# QCopterFC_IMU_Sch.net
KiCad netlist of a schematic drawn in Altium Designer
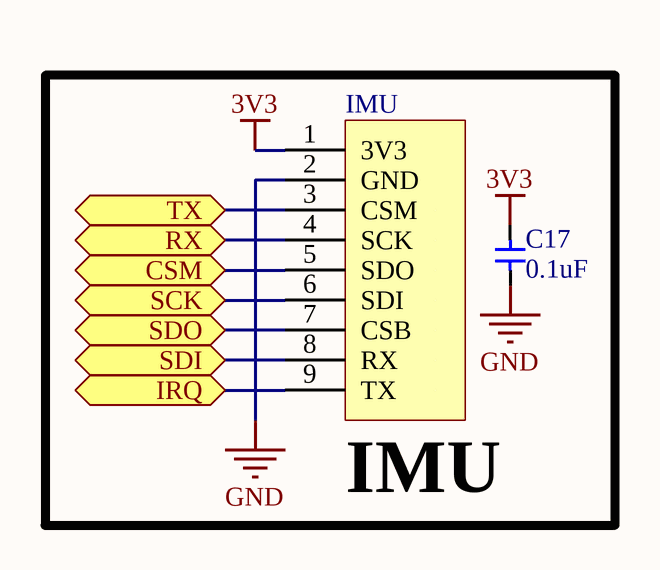
[diagram p0: QCopterFC_IMU_Sch.SchDoc]

(export (version "E")
  (design (tool "Eeschema 10.0.6"))
  (components
    (comp (ref "C17")
      (value "0.1uF")
      (footprint "PCB_Passive:CAP_0603")
      (description "Capacitor")
      (fields (field (name "Comment") "Cap_0603"))
      (libsource (lib "SCH_Passive") (part "Cap_0603"))
    )
    (comp (ref "IMU")
      (value "SmartIMU")
      (footprint "PCB_Module:SMART_IMU")
      (description "Module")
      (libsource (lib "SCH_Module") (part "SmartIMU"))
    )
  )
  (nets
    (net (code "1") (name "/CSM") (class "Default")
      (node (ref "IMU") (pin "5") (pinfunction "SDO_5") (pintype "passive"))
    )
    (net (code "2") (name "/IRQ") (class "Default")
      (node (ref "IMU") (pin "9") (pinfunction "TX_9") (pintype "passive"))
    )
    (net (code "3") (name "/RX") (class "Default")
      (node (ref "IMU") (pin "4") (pinfunction "SCK_4") (pintype "passive"))
    )
    (net (code "4") (name "/SCK") (class "Default")
      (node (ref "IMU") (pin "6") (pinfunction "SDI_6") (pintype "passive"))
    )
    (net (code "5") (name "/SDI") (class "Default")
      (node (ref "IMU") (pin "8") (pinfunction "RX_8") (pintype "passive"))
    )
    (net (code "6") (name "/SDO") (class "Default")
      (node (ref "IMU") (pin "7") (pinfunction "CSB_7") (pintype "passive"))
    )
    (net (code "7") (name "/TX") (class "Default")
      (node (ref "IMU") (pin "3") (pinfunction "CSM_3") (pintype "passive"))
    )
    (net (code "8") (name "3V3") (class "Default")
      (node (ref "C17") (pin "2") (pinfunction "2_2") (pintype "passive"))
      (node (ref "IMU") (pin "1") (pinfunction "3V3_1") (pintype "passive"))
    )
    (net (code "9") (name "GND") (class "Default")
      (node (ref "C17") (pin "1") (pinfunction "1_1") (pintype "passive"))
      (node (ref "IMU") (pin "2") (pinfunction "GND_2") (pintype "passive"))
    )
    (net (code "10") (name "unconnected-(IMU-NC-Pad10)") (class "Default")
      (node (ref "IMU") (pin "10") (pinfunction "NC_10") (pintype "passive"))
    )
    (net (code "11") (name "unconnected-(IMU-NC-Pad11)") (class "Default")
      (node (ref "IMU") (pin "11") (pinfunction "NC_11") (pintype "passive"))
    )
    (net (code "12") (name "unconnected-(IMU-NC-Pad12)") (class "Default")
      (node (ref "IMU") (pin "12") (pinfunction "NC_12") (pintype "passive"))
    )
    (net (code "13") (name "unconnected-(IMU-NC-Pad13)") (class "Default")
      (node (ref "IMU") (pin "13") (pinfunction "NC_13") (pintype "passive"))
    )
    (net (code "14") (name "unconnected-(IMU-NC-Pad14)") (class "Default")
      (node (ref "IMU") (pin "14") (pinfunction "NC_14") (pintype "passive"))
    )
    (net (code "15") (name "unconnected-(IMU-NC-Pad15)") (class "Default")
      (node (ref "IMU") (pin "15") (pinfunction "NC_15") (pintype "passive"))
    )
    (net (code "16") (name "unconnected-(IMU-NC-Pad16)") (class "Default")
      (node (ref "IMU") (pin "16") (pinfunction "NC_16") (pintype "passive"))
    )
  )
)
